# CH32M030C8U7-R0.net
KiCad netlist of a schematic drawn in Altium Designer
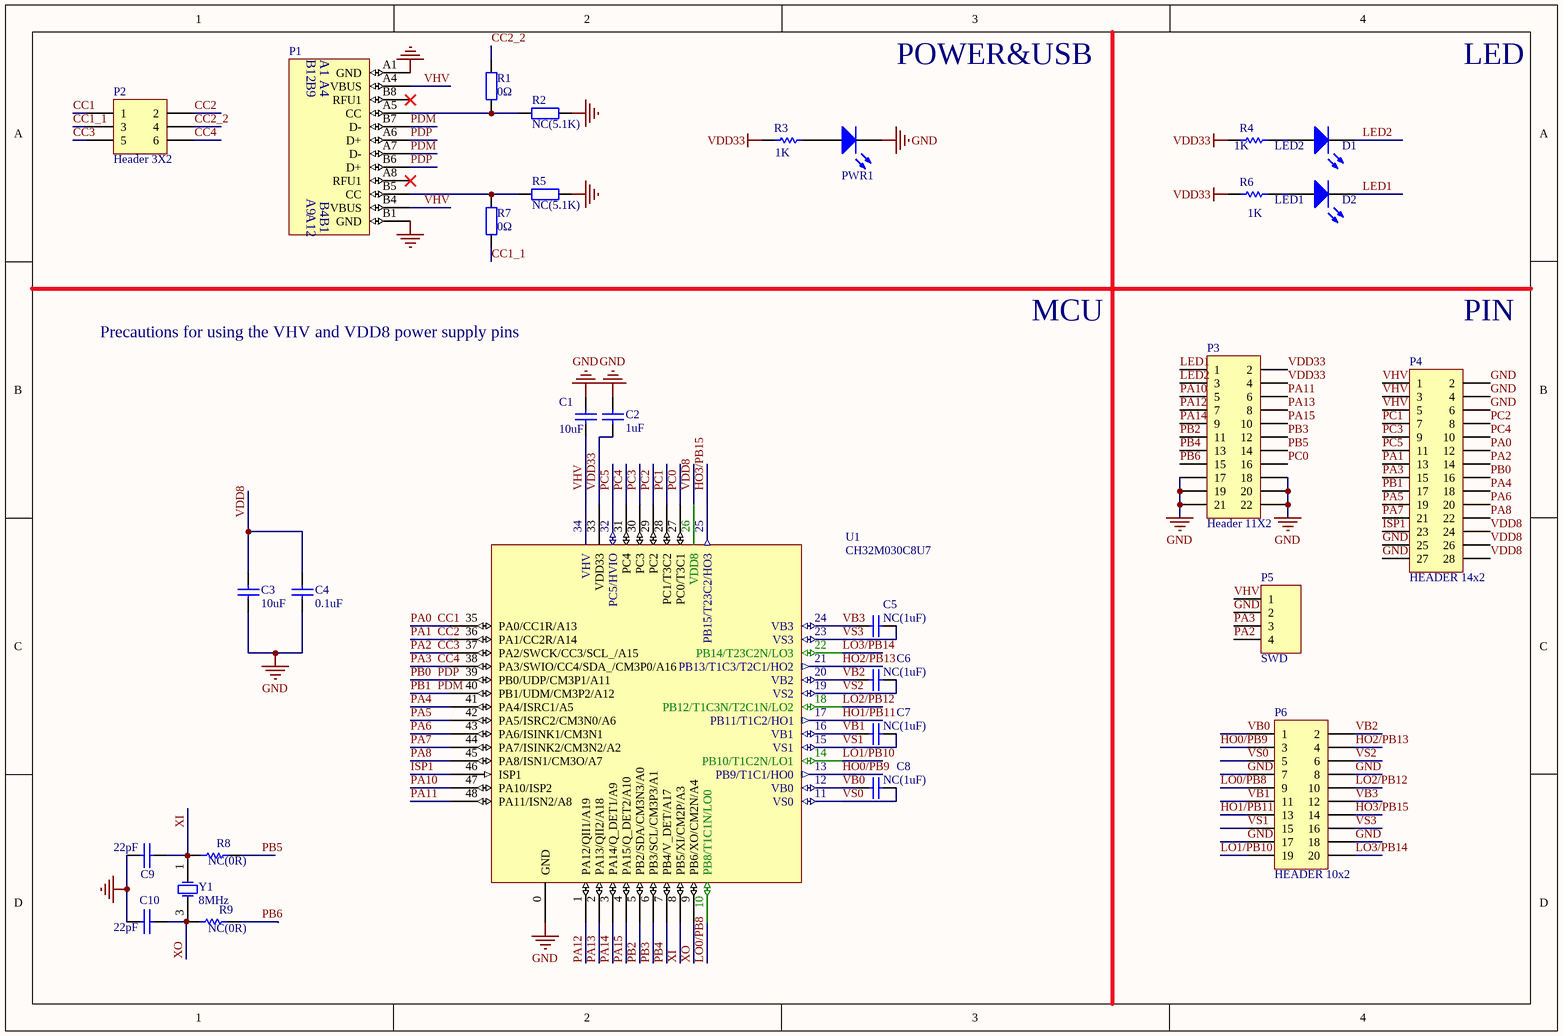
[diagram p0: CH32M030C8U7-R0.SchDoc]

(export (version "E")
  (design (tool "Eeschema 10.0.6"))
  (components
    (comp (ref "C1")
      (value "10uF")
      (footprint "0603_C")
      (description "Capacitor")
      (fields (field (name "PUBLISHER") "Altium Limited"))
      (libsource (lib "*") (part "Cap"))
    )
    (comp (ref "C2")
      (value "1uF")
      (footprint "0603_C")
      (description "Capacitor")
      (fields (field (name "PUBLISHER") "Altium Limited"))
      (libsource (lib "*") (part "Cap"))
    )
    (comp (ref "C3")
      (value "10uF")
      (footprint "0603_C")
      (description "Capacitor")
      (fields (field (name "PUBLISHER") "Altium Limited"))
      (libsource (lib "*") (part "Cap"))
    )
    (comp (ref "C4")
      (value "0.1uF")
      (footprint "0603_C")
      (description "Capacitor")
      (fields (field (name "PUBLISHER") "Altium Limited"))
      (libsource (lib "*") (part "Cap"))
    )
    (comp (ref "C5")
      (value "NC(1uF)")
      (footprint "0603_C")
      (description "Capacitor")
      (fields (field (name "PUBLISHER") "Altium Limited"))
      (libsource (lib "*") (part "Cap"))
    )
    (comp (ref "C6")
      (value "NC(1uF)")
      (footprint "0603_C")
      (description "Capacitor")
      (fields (field (name "PUBLISHER") "Altium Limited"))
      (libsource (lib "*") (part "Cap"))
    )
    (comp (ref "C7")
      (value "NC(1uF)")
      (footprint "0603_C")
      (description "Capacitor")
      (fields (field (name "PUBLISHER") "Altium Limited"))
      (libsource (lib "*") (part "Cap"))
    )
    (comp (ref "C8")
      (value "NC(1uF)")
      (footprint "0603_C")
      (description "Capacitor")
      (fields (field (name "PUBLISHER") "Altium Limited"))
      (libsource (lib "*") (part "Cap"))
    )
    (comp (ref "C9")
      (value "22pF")
      (footprint "0603_C")
      (description "Capacitor")
      (libsource (lib "*") (part "CAP"))
    )
    (comp (ref "C10")
      (value "22pF")
      (footprint "0603_C")
      (description "Capacitor")
      (libsource (lib "*") (part "CAP"))
    )
    (comp (ref "D1")
      (value "LED2")
      (footprint "0603+")
      (description "Typical INFRARED GaAs LED")
      (fields (field (name "PUBLISHER") "Altium Limited"))
      (libsource (lib "*") (part "LED0"))
    )
    (comp (ref "D2")
      (value "LED1")
      (footprint "0603+")
      (description "Typical INFRARED GaAs LED")
      (fields (field (name "PUBLISHER") "Altium Limited"))
      (libsource (lib "*") (part "LED0"))
    )
    (comp (ref "P1")
      (value "TYPE-C")
      (footprint "TYPE-C-Receptacle-2.0")
      (libsource (lib "*") (part "TYPE-C1"))
    )
    (comp (ref "P2")
      (value "Header 3X2")
      (footprint "IDC6-2.54mm")
      (description "Header, 3-Pin, Dual row")
      (fields (field (name "PUBLISHER") "Altium Limited"))
      (libsource (lib "Miscellaneous Connectors") (part "Header 3X2"))
    )
    (comp (ref "P3")
      (value "Header 11X2")
      (footprint "IDC22-2.54mm")
      (description "Header, 11-Pin, Dual row")
      (fields (field (name "PUBLISHER") "Altium Limited"))
      (libsource (lib "Miscellaneous Connectors") (part "Header 11X2"))
    )
    (comp (ref "P4")
      (value "HEADER 14x2")
      (footprint "MYPCB:IDC28-2.54MM")
      (description "Header, 14-Pin, Dual row")
      (libsource (lib "wch_sch_others") (part "HEADER 14x2"))
    )
    (comp (ref "P5")
      (value "SWD")
      (footprint "SIP4-2.54mm")
      (description "Header, 4-Pin")
      (libsource (lib "wch_sch_others") (part "HEADER 4"))
    )
    (comp (ref "P6")
      (value "HEADER 10x2")
      (footprint "MYPCB:IDC20-2.54MM")
      (description "Header, 10-Pin, Dual row")
      (libsource (lib "wch_sch_others") (part "HEADER 10x2"))
    )
    (comp (ref "PWR1")
      (value "POWER  red")
      (footprint "0603+")
      (description "Typical INFRARED GaAs LED")
      (fields (field (name "PUBLISHER") "Altium Limited"))
      (libsource (lib "*") (part "LED0"))
    )
    (comp (ref "R1")
      (value "0Ω")
      (footprint "0603")
      (description "Resistor")
      (libsource (lib "Miscellaneous Devices") (part "Res2"))
    )
    (comp (ref "R2")
      (value "NC(5.1K)")
      (footprint "0603")
      (description "Resistor")
      (libsource (lib "") (part "Res2_1"))
    )
    (comp (ref "R3")
      (value "1K")
      (footprint "0603")
      (description "Semiconductor Resistor")
      (fields (field (name "PUBLISHER") "Altium Limited"))
      (libsource (lib "*") (part "Res Semi"))
    )
    (comp (ref "R4")
      (value "1K")
      (footprint "0603")
      (description "Semiconductor Resistor")
      (fields (field (name "PUBLISHER") "Altium Limited"))
      (libsource (lib "*") (part "Res Semi"))
    )
    (comp (ref "R5")
      (value "NC(5.1K)")
      (footprint "0603")
      (description "Resistor")
      (libsource (lib "") (part "Res2_1"))
    )
    (comp (ref "R6")
      (value "1K")
      (footprint "0603")
      (description "Semiconductor Resistor")
      (fields (field (name "PUBLISHER") "Altium Limited"))
      (libsource (lib "*") (part "Res Semi"))
    )
    (comp (ref "R7")
      (value "0Ω")
      (footprint "0603")
      (description "Resistor")
      (libsource (lib "Miscellaneous Devices") (part "Res2"))
    )
    (comp (ref "R8")
      (value "NC(0R)")
      (footprint "0603")
      (description "Semiconductor Resistor")
      (fields (field (name "PUBLISHER") "Altium Limited"))
      (libsource (lib "*") (part "Res Semi"))
    )
    (comp (ref "R9")
      (value "NC(0R)")
      (footprint "0603")
      (description "Semiconductor Resistor")
      (fields (field (name "PUBLISHER") "Altium Limited"))
      (libsource (lib "*") (part "Res Semi"))
    )
    (comp (ref "U1")
      (value "CH32M030C8U7")
      (footprint "QFN48_5X5")
      (description "RISC-V MCU, 72MHz, USB, Type-C/PD, OPA, CMP, 28V gate driver")
      (libsource (lib "CHXXX") (part "CH32M030C8U7"))
    )
    (comp (ref "Y1")
      (value "8MHz")
      (footprint "XT3225")
      (description "Crystal Oscillator")
      (fields (field (name "PUBLISHER") "Altium Limited"))
      (libsource (lib "*") (part "XTAL"))
    )
  )
  (nets
    (net (code "1") (name "/CC1") (class "Default")
      (node (ref "P2") (pin "1") (pinfunction "1_1") (pintype "passive"))
      (node (ref "P4") (pin "12") (pinfunction "12_12") (pintype "passive"))
      (node (ref "U1") (pin "35") (pinfunction "PA0/CC1R/A13_35") (pintype "bidirectional"))
    )
    (net (code "2") (name "/CC1_1") (class "Default")
      (node (ref "P2") (pin "3") (pinfunction "3_3") (pintype "passive"))
      (node (ref "R7") (pin "1") (pinfunction "1_1") (pintype "passive"))
    )
    (net (code "3") (name "/CC2") (class "Default")
      (node (ref "P2") (pin "2") (pinfunction "2_2") (pintype "passive"))
      (node (ref "P4") (pin "13") (pinfunction "13_13") (pintype "passive"))
      (node (ref "U1") (pin "36") (pinfunction "PA1/CC2R/A14_36") (pintype "bidirectional"))
    )
    (net (code "4") (name "/CC2_2") (class "Default")
      (node (ref "P2") (pin "4") (pinfunction "4_4") (pintype "passive"))
      (node (ref "R1") (pin "2") (pinfunction "2_2") (pintype "passive"))
    )
    (net (code "5") (name "/CC3") (class "Default")
      (node (ref "P2") (pin "5") (pinfunction "5_5") (pintype "passive"))
      (node (ref "P4") (pin "14") (pinfunction "14_14") (pintype "passive"))
      (node (ref "P5") (pin "4") (pinfunction "4_4") (pintype "passive"))
      (node (ref "U1") (pin "37") (pinfunction "PA2/SWCK/CC3/SCL_/A15_37") (pintype "bidirectional"))
    )
    (net (code "6") (name "/CC4") (class "Default")
      (node (ref "P2") (pin "6") (pinfunction "6_6") (pintype "passive"))
      (node (ref "P4") (pin "15") (pinfunction "15_15") (pintype "passive"))
      (node (ref "P5") (pin "3") (pinfunction "3_3") (pintype "passive"))
      (node (ref "U1") (pin "38") (pinfunction "PA3/SWIO/CC4/SDA_/CM3P0/A16_38") (pintype "bidirectional"))
    )
    (net (code "7") (name "/HO0{slash}PB9") (class "Default")
      (node (ref "P6") (pin "3") (pinfunction "3_3") (pintype "passive"))
      (node (ref "U1") (pin "13") (pinfunction "PB9/T1C1/HO0_13") (pintype "output"))
    )
    (net (code "8") (name "/HO1{slash}PB11") (class "Default")
      (node (ref "P6") (pin "13") (pinfunction "13_13") (pintype "passive"))
      (node (ref "U1") (pin "17") (pinfunction "PB11/T1C2/HO1_17") (pintype "output"))
    )
    (net (code "9") (name "/HO2{slash}PB13") (class "Default")
      (node (ref "P6") (pin "4") (pinfunction "4_4") (pintype "passive"))
      (node (ref "U1") (pin "21") (pinfunction "PB13/T1C3/T2C1/HO2_21") (pintype "output"))
    )
    (net (code "10") (name "/HO3{slash}PB15") (class "Default")
      (node (ref "P6") (pin "14") (pinfunction "14_14") (pintype "passive"))
      (node (ref "U1") (pin "25") (pinfunction "PB15/T23C2/HO3_25") (pintype "output"))
    )
    (net (code "11") (name "/ISP1") (class "Default")
      (node (ref "P4") (pin "23") (pinfunction "23_23") (pintype "passive"))
      (node (ref "U1") (pin "46") (pinfunction "ISP1_46") (pintype "input"))
    )
    (net (code "12") (name "/LED1") (class "Default")
      (node (ref "D2") (pin "2") (pinfunction "K_2") (pintype "passive"))
      (node (ref "P3") (pin "1") (pinfunction "1_1") (pintype "passive"))
    )
    (net (code "13") (name "/LED2") (class "Default")
      (node (ref "D1") (pin "2") (pinfunction "K_2") (pintype "passive"))
      (node (ref "P3") (pin "3") (pinfunction "3_3") (pintype "passive"))
    )
    (net (code "14") (name "/LO0{slash}PB8") (class "Default")
      (node (ref "P6") (pin "9") (pinfunction "9_9") (pintype "passive"))
      (node (ref "U1") (pin "10") (pinfunction "PB8/T1C1N/LO0_10") (pintype "bidirectional"))
    )
    (net (code "15") (name "/LO1{slash}PB10") (class "Default")
      (node (ref "P6") (pin "19") (pinfunction "19_19") (pintype "passive"))
      (node (ref "U1") (pin "14") (pinfunction "PB10/T1C2N/LO1_14") (pintype "bidirectional"))
    )
    (net (code "16") (name "/LO2{slash}PB12") (class "Default")
      (node (ref "P6") (pin "10") (pinfunction "10_10") (pintype "passive"))
      (node (ref "U1") (pin "18") (pinfunction "PB12/T1C3N/T2C1N/LO2_18") (pintype "bidirectional"))
    )
    (net (code "17") (name "/LO3{slash}PB14") (class "Default")
      (node (ref "P6") (pin "20") (pinfunction "20_20") (pintype "passive"))
      (node (ref "U1") (pin "22") (pinfunction "PB14/T23C2N/LO3_22") (pintype "bidirectional"))
    )
    (net (code "18") (name "/PA4") (class "Default")
      (node (ref "P4") (pin "18") (pinfunction "18_18") (pintype "passive"))
      (node (ref "U1") (pin "41") (pinfunction "PA4/ISRC1/A5_41") (pintype "bidirectional"))
    )
    (net (code "19") (name "/PA5") (class "Default")
      (node (ref "P4") (pin "19") (pinfunction "19_19") (pintype "passive"))
      (node (ref "U1") (pin "42") (pinfunction "PA5/ISRC2/CM3N0/A6_42") (pintype "bidirectional"))
    )
    (net (code "20") (name "/PA6") (class "Default")
      (node (ref "P4") (pin "20") (pinfunction "20_20") (pintype "passive"))
      (node (ref "U1") (pin "43") (pinfunction "PA6/ISINK1/CM3N1_43") (pintype "bidirectional"))
    )
    (net (code "21") (name "/PA7") (class "Default")
      (node (ref "P4") (pin "21") (pinfunction "21_21") (pintype "passive"))
      (node (ref "U1") (pin "44") (pinfunction "PA7/ISINK2/CM3N2/A2_44") (pintype "bidirectional"))
    )
    (net (code "22") (name "/PA8") (class "Default")
      (node (ref "P4") (pin "22") (pinfunction "22_22") (pintype "passive"))
      (node (ref "U1") (pin "45") (pinfunction "PA8/ISN1/CM3O/A7_45") (pintype "bidirectional"))
    )
    (net (code "23") (name "/PA10") (class "Default")
      (node (ref "P3") (pin "5") (pinfunction "5_5") (pintype "passive"))
      (node (ref "U1") (pin "47") (pinfunction "PA10/ISP2_47") (pintype "bidirectional"))
    )
    (net (code "24") (name "/PA11") (class "Default")
      (node (ref "P3") (pin "6") (pinfunction "6_6") (pintype "passive"))
      (node (ref "U1") (pin "48") (pinfunction "PA11/ISN2/A8_48") (pintype "bidirectional"))
    )
    (net (code "25") (name "/PA12") (class "Default")
      (node (ref "P3") (pin "7") (pinfunction "7_7") (pintype "passive"))
      (node (ref "U1") (pin "1") (pinfunction "PA12/QII1/A19_1") (pintype "bidirectional"))
    )
    (net (code "26") (name "/PA13") (class "Default")
      (node (ref "P3") (pin "8") (pinfunction "8_8") (pintype "passive"))
      (node (ref "U1") (pin "2") (pinfunction "PA13/QII2/A18_2") (pintype "bidirectional"))
    )
    (net (code "27") (name "/PA14") (class "Default")
      (node (ref "P3") (pin "9") (pinfunction "9_9") (pintype "passive"))
      (node (ref "U1") (pin "3") (pinfunction "PA14/Q_DET1/A9_3") (pintype "bidirectional"))
    )
    (net (code "28") (name "/PA15") (class "Default")
      (node (ref "P3") (pin "10") (pinfunction "10_10") (pintype "passive"))
      (node (ref "U1") (pin "4") (pinfunction "PA15/Q_DET2/A10_4") (pintype "bidirectional"))
    )
    (net (code "29") (name "/PB0") (class "Default")
      (node (ref "P1") (pin "A6") (pinfunction "D+_A6") (pintype "bidirectional"))
      (node (ref "P1") (pin "B6") (pinfunction "D+_B6") (pintype "bidirectional"))
      (node (ref "P4") (pin "16") (pinfunction "16_16") (pintype "passive"))
      (node (ref "U1") (pin "39") (pinfunction "PB0/UDP/CM3P1/A11_39") (pintype "bidirectional"))
    )
    (net (code "30") (name "/PB1") (class "Default")
      (node (ref "P1") (pin "A7") (pinfunction "D-_A7") (pintype "bidirectional"))
      (node (ref "P1") (pin "B7") (pinfunction "D-_B7") (pintype "bidirectional"))
      (node (ref "P4") (pin "17") (pinfunction "17_17") (pintype "passive"))
      (node (ref "U1") (pin "40") (pinfunction "PB1/UDM/CM3P2/A12_40") (pintype "bidirectional"))
    )
    (net (code "31") (name "/PB2") (class "Default")
      (node (ref "P3") (pin "11") (pinfunction "11_11") (pintype "passive"))
      (node (ref "U1") (pin "5") (pinfunction "PB2/SDA/CM3N3/A0_5") (pintype "bidirectional"))
    )
    (net (code "32") (name "/PB3") (class "Default")
      (node (ref "P3") (pin "12") (pinfunction "12_12") (pintype "passive"))
      (node (ref "U1") (pin "6") (pinfunction "PB3/SCL/CM3P3/A1_6") (pintype "bidirectional"))
    )
    (net (code "33") (name "/PB4") (class "Default")
      (node (ref "P3") (pin "13") (pinfunction "13_13") (pintype "passive"))
      (node (ref "U1") (pin "7") (pinfunction "PB4/V_DET/A17_7") (pintype "bidirectional"))
    )
    (net (code "34") (name "/PB5") (class "Default")
      (node (ref "P3") (pin "14") (pinfunction "14_14") (pintype "passive"))
      (node (ref "R8") (pin "2") (pinfunction "2_2") (pintype "passive"))
    )
    (net (code "35") (name "/PB6") (class "Default")
      (node (ref "P3") (pin "15") (pinfunction "15_15") (pintype "passive"))
      (node (ref "R9") (pin "2") (pinfunction "2_2") (pintype "passive"))
    )
    (net (code "36") (name "/PC0") (class "Default")
      (node (ref "P3") (pin "16") (pinfunction "16_16") (pintype "passive"))
      (node (ref "U1") (pin "27") (pinfunction "PC0/T3C1_27") (pintype "bidirectional"))
    )
    (net (code "37") (name "/PC1") (class "Default")
      (node (ref "P4") (pin "7") (pinfunction "7_7") (pintype "passive"))
      (node (ref "U1") (pin "28") (pinfunction "PC1/T3C2_28") (pintype "bidirectional"))
    )
    (net (code "38") (name "/PC2") (class "Default")
      (node (ref "P4") (pin "8") (pinfunction "8_8") (pintype "passive"))
      (node (ref "U1") (pin "29") (pinfunction "PC2_29") (pintype "bidirectional"))
    )
    (net (code "39") (name "/PC3") (class "Default")
      (node (ref "P4") (pin "9") (pinfunction "9_9") (pintype "passive"))
      (node (ref "U1") (pin "30") (pinfunction "PC3_30") (pintype "bidirectional"))
    )
    (net (code "40") (name "/PC4") (class "Default")
      (node (ref "P4") (pin "10") (pinfunction "10_10") (pintype "passive"))
      (node (ref "U1") (pin "31") (pinfunction "PC4_31") (pintype "bidirectional"))
    )
    (net (code "41") (name "/PC5") (class "Default")
      (node (ref "P4") (pin "11") (pinfunction "11_11") (pintype "passive"))
      (node (ref "U1") (pin "32") (pinfunction "PC5/HVIO_32") (pintype "bidirectional"))
    )
    (net (code "42") (name "/VB0") (class "Default")
      (node (ref "C8") (pin "2") (pinfunction "2_2") (pintype "passive"))
      (node (ref "P6") (pin "1") (pinfunction "1_1") (pintype "passive"))
      (node (ref "U1") (pin "12") (pinfunction "VB0_12") (pintype "bidirectional"))
    )
    (net (code "43") (name "/VB1") (class "Default")
      (node (ref "C7") (pin "2") (pinfunction "2_2") (pintype "passive"))
      (node (ref "P6") (pin "11") (pinfunction "11_11") (pintype "passive"))
      (node (ref "U1") (pin "16") (pinfunction "VB1_16") (pintype "bidirectional"))
    )
    (net (code "44") (name "/VB2") (class "Default")
      (node (ref "C6") (pin "2") (pinfunction "2_2") (pintype "passive"))
      (node (ref "P6") (pin "2") (pinfunction "2_2") (pintype "passive"))
      (node (ref "U1") (pin "20") (pinfunction "VB2_20") (pintype "bidirectional"))
    )
    (net (code "45") (name "/VB3") (class "Default")
      (node (ref "C5") (pin "2") (pinfunction "2_2") (pintype "passive"))
      (node (ref "P6") (pin "12") (pinfunction "12_12") (pintype "passive"))
      (node (ref "U1") (pin "24") (pinfunction "VB3_24") (pintype "bidirectional"))
    )
    (net (code "46") (name "/VDD8") (class "Default")
      (node (ref "C3") (pin "2") (pinfunction "2_2") (pintype "passive"))
      (node (ref "C4") (pin "2") (pinfunction "2_2") (pintype "passive"))
      (node (ref "P4") (pin "24") (pinfunction "24_24") (pintype "passive"))
      (node (ref "P4") (pin "26") (pinfunction "26_26") (pintype "passive"))
      (node (ref "P4") (pin "28") (pinfunction "28_28") (pintype "passive"))
      (node (ref "U1") (pin "26") (pinfunction "VDD8_26") (pintype "power_in"))
    )
    (net (code "47") (name "/VHV") (class "Default")
      (node (ref "C1") (pin "1") (pinfunction "1_1") (pintype "passive"))
      (node (ref "P1") (pin "A4") (pinfunction "VBUS_A4") (pintype "bidirectional"))
      (node (ref "P1") (pin "B4") (pinfunction "VBUS_B4") (pintype "bidirectional"))
      (node (ref "P4") (pin "1") (pinfunction "1_1") (pintype "passive"))
      (node (ref "P4") (pin "3") (pinfunction "3_3") (pintype "passive"))
      (node (ref "P4") (pin "5") (pinfunction "5_5") (pintype "passive"))
      (node (ref "P5") (pin "1") (pinfunction "1_1") (pintype "passive"))
      (node (ref "U1") (pin "34") (pinfunction "VHV_34") (pintype "power_in"))
    )
    (net (code "48") (name "/VS0") (class "Default")
      (node (ref "C8") (pin "1") (pinfunction "1_1") (pintype "passive"))
      (node (ref "P6") (pin "5") (pinfunction "5_5") (pintype "passive"))
      (node (ref "U1") (pin "11") (pinfunction "VS0_11") (pintype "bidirectional"))
    )
    (net (code "49") (name "/VS1") (class "Default")
      (node (ref "C7") (pin "1") (pinfunction "1_1") (pintype "passive"))
      (node (ref "P6") (pin "15") (pinfunction "15_15") (pintype "passive"))
      (node (ref "U1") (pin "15") (pinfunction "VS1_15") (pintype "bidirectional"))
    )
    (net (code "50") (name "/VS2") (class "Default")
      (node (ref "C6") (pin "1") (pinfunction "1_1") (pintype "passive"))
      (node (ref "P6") (pin "6") (pinfunction "6_6") (pintype "passive"))
      (node (ref "U1") (pin "19") (pinfunction "VS2_19") (pintype "bidirectional"))
    )
    (net (code "51") (name "/VS3") (class "Default")
      (node (ref "C5") (pin "1") (pinfunction "1_1") (pintype "passive"))
      (node (ref "P6") (pin "16") (pinfunction "16_16") (pintype "passive"))
      (node (ref "U1") (pin "23") (pinfunction "VS3_23") (pintype "bidirectional"))
    )
    (net (code "52") (name "/XI") (class "Default")
      (node (ref "C9") (pin "2") (pinfunction "2_2") (pintype "passive"))
      (node (ref "R8") (pin "1") (pinfunction "1_1") (pintype "passive"))
      (node (ref "U1") (pin "8") (pinfunction "PB5/XI/CM2P/A3_8") (pintype "bidirectional"))
      (node (ref "Y1") (pin "1") (pinfunction "OSC1_1") (pintype "passive"))
    )
    (net (code "53") (name "/XO") (class "Default")
      (node (ref "C10") (pin "2") (pinfunction "2_2") (pintype "passive"))
      (node (ref "R9") (pin "1") (pinfunction "1_1") (pintype "passive"))
      (node (ref "U1") (pin "9") (pinfunction "PB6/XO/CM2N/A4_9") (pintype "bidirectional"))
    )
    (net (code "54") (name "GND") (class "Default")
      (node (ref "C1") (pin "2") (pinfunction "2_2") (pintype "passive"))
      (node (ref "C10") (pin "1") (pinfunction "1_1") (pintype "passive"))
      (node (ref "C2") (pin "2") (pinfunction "2_2") (pintype "passive"))
      (node (ref "C3") (pin "1") (pinfunction "1_1") (pintype "passive"))
      (node (ref "C4") (pin "1") (pinfunction "1_1") (pintype "passive"))
      (node (ref "C9") (pin "1") (pinfunction "1_1") (pintype "passive"))
      (node (ref "P1") (pin "A1") (pinfunction "GND_A1") (pintype "bidirectional"))
      (node (ref "P1") (pin "B1") (pinfunction "GND_B1") (pintype "bidirectional"))
      (node (ref "P3") (pin "17") (pinfunction "17_17") (pintype "passive"))
      (node (ref "P3") (pin "18") (pinfunction "18_18") (pintype "passive"))
      (node (ref "P3") (pin "19") (pinfunction "19_19") (pintype "passive"))
      (node (ref "P3") (pin "20") (pinfunction "20_20") (pintype "passive"))
      (node (ref "P3") (pin "21") (pinfunction "21_21") (pintype "passive"))
      (node (ref "P3") (pin "22") (pinfunction "22_22") (pintype "passive"))
      (node (ref "P4") (pin "2") (pinfunction "2_2") (pintype "passive"))
      (node (ref "P4") (pin "25") (pinfunction "25_25") (pintype "passive"))
      (node (ref "P4") (pin "27") (pinfunction "27_27") (pintype "passive"))
      (node (ref "P4") (pin "4") (pinfunction "4_4") (pintype "passive"))
      (node (ref "P4") (pin "6") (pinfunction "6_6") (pintype "passive"))
      (node (ref "P5") (pin "2") (pinfunction "2_2") (pintype "passive"))
      (node (ref "P6") (pin "17") (pinfunction "17_17") (pintype "passive"))
      (node (ref "P6") (pin "18") (pinfunction "18_18") (pintype "passive"))
      (node (ref "P6") (pin "7") (pinfunction "7_7") (pintype "passive"))
      (node (ref "P6") (pin "8") (pinfunction "8_8") (pintype "passive"))
      (node (ref "PWR1") (pin "2") (pinfunction "K_2") (pintype "passive"))
      (node (ref "R2") (pin "2") (pinfunction "2_2") (pintype "passive"))
      (node (ref "R5") (pin "2") (pinfunction "2_2") (pintype "passive"))
      (node (ref "U1") (pin "0") (pinfunction "GND_0") (pintype "power_in"))
    )
    (net (code "55") (name "Net-(D1-A)") (class "Default")
      (node (ref "D1") (pin "1") (pinfunction "A_1") (pintype "passive"))
      (node (ref "R4") (pin "2") (pinfunction "2_2") (pintype "passive"))
    )
    (net (code "56") (name "Net-(D2-A)") (class "Default")
      (node (ref "D2") (pin "1") (pinfunction "A_1") (pintype "passive"))
      (node (ref "R6") (pin "2") (pinfunction "2_2") (pintype "passive"))
    )
    (net (code "57") (name "Net-(P1-CC-PadA5)") (class "Default")
      (node (ref "P1") (pin "A5") (pinfunction "CC_A5") (pintype "bidirectional"))
      (node (ref "R1") (pin "1") (pinfunction "1_1") (pintype "passive"))
      (node (ref "R2") (pin "1") (pinfunction "1_1") (pintype "passive"))
    )
    (net (code "58") (name "Net-(P1-CC-PadB5)") (class "Default")
      (node (ref "P1") (pin "B5") (pinfunction "CC_B5") (pintype "bidirectional"))
      (node (ref "R5") (pin "1") (pinfunction "1_1") (pintype "passive"))
      (node (ref "R7") (pin "2") (pinfunction "2_2") (pintype "passive"))
    )
    (net (code "59") (name "Net-(PWR1-A)") (class "Default")
      (node (ref "PWR1") (pin "1") (pinfunction "A_1") (pintype "passive"))
      (node (ref "R3") (pin "1") (pinfunction "1_1") (pintype "passive"))
    )
    (net (code "60") (name "VDD33") (class "Default")
      (node (ref "C2") (pin "1") (pinfunction "1_1") (pintype "passive"))
      (node (ref "P3") (pin "2") (pinfunction "2_2") (pintype "passive"))
      (node (ref "P3") (pin "4") (pinfunction "4_4") (pintype "passive"))
      (node (ref "R3") (pin "2") (pinfunction "2_2") (pintype "passive"))
      (node (ref "R4") (pin "1") (pinfunction "1_1") (pintype "passive"))
      (node (ref "R6") (pin "1") (pinfunction "1_1") (pintype "passive"))
      (node (ref "U1") (pin "33") (pinfunction "VDD33_33") (pintype "power_in"))
    )
    (net (code "61") (name "unconnected-(P1-RFU1-PadA8)") (class "Default")
      (node (ref "P1") (pin "A8") (pinfunction "RFU1_A8") (pintype "bidirectional+no_connect"))
    )
    (net (code "62") (name "unconnected-(P1-RFU1-PadB8)") (class "Default")
      (node (ref "P1") (pin "B8") (pinfunction "RFU1_B8") (pintype "bidirectional+no_connect"))
    )
    (net (code "63") (name "unconnected-(Y1-OSC2-Pad3)") (class "Default")
      (node (ref "Y1") (pin "3") (pinfunction "OSC2_3") (pintype "passive"))
    )
  )
)
